# CH32V003F4P6-R0-1v1.net
KiCad netlist of a schematic drawn in Altium Designer
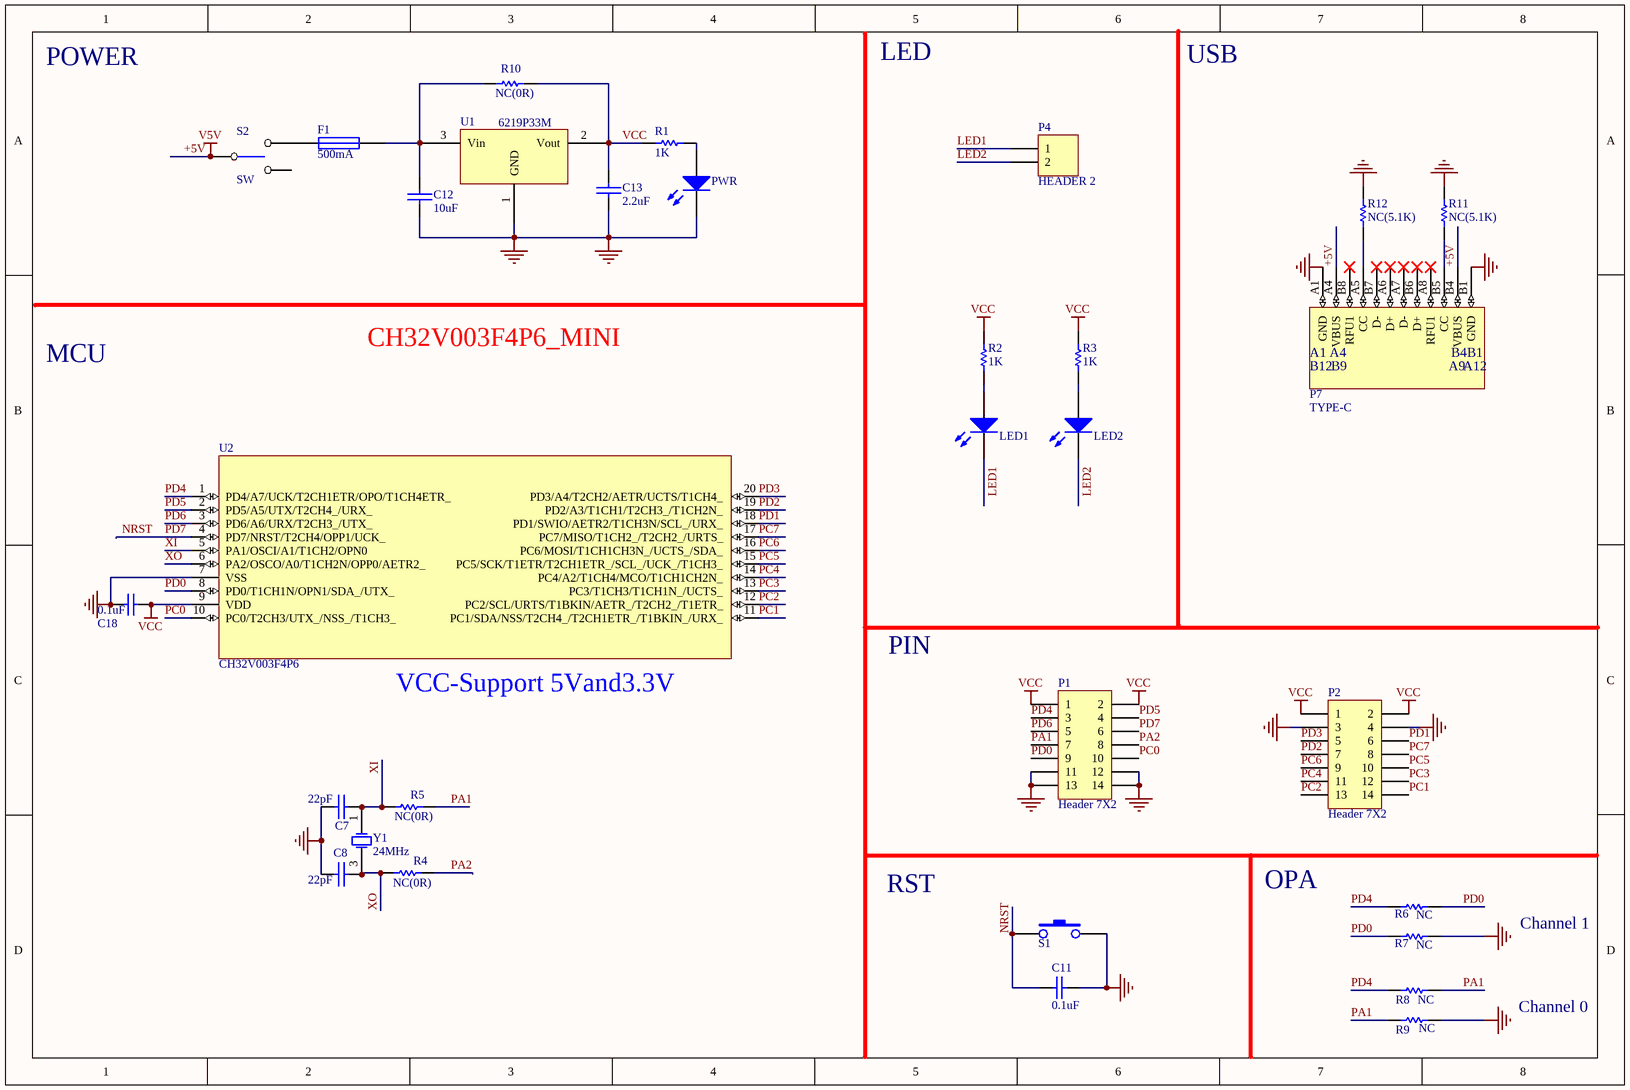
[diagram p0: CH32V003F4P6-R0-1v1.SchDoc]

(export (version "E")
  (design (tool "Eeschema 10.0.6"))
  (components
    (comp (ref "C7")
      (value "22pF")
      (footprint "0603_C")
      (description "Capacitor")
      (libsource (lib "*") (part "CAP"))
    )
    (comp (ref "C8")
      (value "22pF")
      (footprint "0603_C")
      (description "Capacitor")
      (libsource (lib "*") (part "CAP"))
    )
    (comp (ref "C11")
      (value "0.1uF")
      (footprint "0603_C")
      (description "Capacitor")
      (fields (field (name "PUBLISHER") "Altium Limited"))
      (libsource (lib "*") (part "Cap"))
    )
    (comp (ref "C12")
      (value "10uF")
      (footprint "3216_C")
      (description "Capacitor")
      (libsource (lib "wch_sch_others") (part "CAP"))
    )
    (comp (ref "C13")
      (value "2.2uF")
      (footprint "0603_C")
      (description "Capacitor")
      (libsource (lib "wch_sch_others") (part "CAP"))
    )
    (comp (ref "C18")
      (value "0.1uF")
      (footprint "0603_C")
      (description "Capacitor")
      (fields (field (name "PUBLISHER") "Altium Limited"))
      (libsource (lib "*") (part "Cap"))
    )
    (comp (ref "F1")
      (value "500mA")
      (footprint "0603")
      (description "Fuse")
      (libsource (lib "*") (part "FUSE1"))
    )
    (comp (ref "LED1")
      (value "LED1   blue")
      (footprint "0603+")
      (description "Typical INFRARED GaAs LED")
      (fields (field (name "PUBLISHER") "Altium Limited"))
      (libsource (lib "*") (part "LED0"))
    )
    (comp (ref "LED2")
      (value "LED2  blue")
      (footprint "0603+")
      (description "Typical INFRARED GaAs LED")
      (fields (field (name "PUBLISHER") "Altium Limited"))
      (libsource (lib "*") (part "LED0"))
    )
    (comp (ref "P1")
      (value "Header 7X2")
      (footprint "IDC14-2.54mm")
      (description "Header, 7-Pin, Dual row")
      (fields (field (name "PUBLISHER") "Altium Limited"))
      (libsource (lib "Miscellaneous Connectors") (part "Header 7X2"))
    )
    (comp (ref "P2")
      (value "Header 7X2")
      (footprint "IDC14-2.54mm")
      (description "Header, 7-Pin, Dual row")
      (fields (field (name "PUBLISHER") "Altium Limited"))
      (libsource (lib "Miscellaneous Connectors") (part "Header 7X2"))
    )
    (comp (ref "P4")
      (value "HEADER 2")
      (footprint "MYPCB:SIP2-2.54mm")
      (description "Header, 2-Pin")
      (libsource (lib "wch_sch_others") (part "HEADER 2"))
    )
    (comp (ref "P7")
      (value "TYPE-C")
      (footprint "TYPE-C-Receptacle-2.0")
      (libsource (lib "*") (part "TYPE-C1"))
    )
    (comp (ref "PWR")
      (value "POWER  red")
      (footprint "0603+")
      (description "Typical INFRARED GaAs LED")
      (fields (field (name "PUBLISHER") "Altium Limited"))
      (libsource (lib "") (part "LED0_1"))
    )
    (comp (ref "R1")
      (value "1K")
      (footprint "0603")
      (description "Semiconductor Resistor")
      (fields (field (name "PUBLISHER") "Altium Limited"))
      (libsource (lib "*") (part "Res Semi"))
    )
    (comp (ref "R2")
      (value "1K")
      (footprint "0603")
      (description "Semiconductor Resistor")
      (fields (field (name "PUBLISHER") "Altium Limited"))
      (libsource (lib "*") (part "Res Semi"))
    )
    (comp (ref "R3")
      (value "1K")
      (footprint "0603")
      (description "Semiconductor Resistor")
      (fields (field (name "PUBLISHER") "Altium Limited"))
      (libsource (lib "*") (part "Res Semi"))
    )
    (comp (ref "R4")
      (value "NC(0R)")
      (footprint "0603")
      (description "Semiconductor Resistor")
      (fields (field (name "Comment") "0R") (field (name "PUBLISHER") "Altium Limited"))
      (libsource (lib "*") (part "Res Semi"))
    )
    (comp (ref "R5")
      (value "NC(0R)")
      (footprint "0603")
      (description "Semiconductor Resistor")
      (fields (field (name "Comment") "0R") (field (name "PUBLISHER") "Altium Limited"))
      (libsource (lib "*") (part "Res Semi"))
    )
    (comp (ref "R6")
      (value "NC")
      (footprint "0603")
      (description "Semiconductor Resistor")
      (fields (field (name "Comment") "0R") (field (name "PUBLISHER") "Altium Limited"))
      (libsource (lib "*") (part "Res Semi"))
    )
    (comp (ref "R7")
      (value "NC")
      (footprint "0603")
      (description "Semiconductor Resistor")
      (fields (field (name "Comment") "0R") (field (name "PUBLISHER") "Altium Limited"))
      (libsource (lib "*") (part "Res Semi"))
    )
    (comp (ref "R8")
      (value "NC")
      (footprint "0603")
      (description "Semiconductor Resistor")
      (fields (field (name "Comment") "0R") (field (name "PUBLISHER") "Altium Limited"))
      (libsource (lib "*") (part "Res Semi"))
    )
    (comp (ref "R9")
      (value "NC")
      (footprint "0603")
      (description "Semiconductor Resistor")
      (fields (field (name "Comment") "0R") (field (name "PUBLISHER") "Altium Limited"))
      (libsource (lib "*") (part "Res Semi"))
    )
    (comp (ref "R10")
      (value "NC(0R)")
      (footprint "0603")
      (description "Semiconductor Resistor")
      (fields (field (name "Comment") "0R") (field (name "PUBLISHER") "Altium Limited"))
      (libsource (lib "*") (part "Res Semi"))
    )
    (comp (ref "R11")
      (value "NC(5.1K)")
      (footprint "0603")
      (description "Semiconductor Resistor")
      (fields (field (name "Comment") "0R") (field (name "PUBLISHER") "Altium Limited"))
      (libsource (lib "*") (part "Res Semi"))
    )
    (comp (ref "R12")
      (value "NC(5.1K)")
      (footprint "0603")
      (description "Semiconductor Resistor")
      (fields (field (name "Comment") "0R") (field (name "PUBLISHER") "Altium Limited"))
      (libsource (lib "*") (part "Res Semi"))
    )
    (comp (ref "S1") (value "NRST") (footprint "SMD_6.1x3.65x2.5mm-KEY") (libsource (lib "*") (part "KEY")))
    (comp (ref "S2") (value "SW") (footprint "SW1") (libsource (lib "*") (part "SW")))
    (comp (ref "U1")
      (value "6219P33M")
      (footprint "SOT-23")
      (libsource (lib "wch_sch_others") (part "6219P33M"))
    )
    (comp (ref "U2")
      (value "CH32V003F4P6")
      (description "RISC-V MCU, 48MHz")
      (libsource (lib "MEXXX") (part "CH32V003F4P6"))
    )
    (comp (ref "Y1")
      (value "24MHz")
      (footprint "XT3225")
      (description "Crystal Oscillator")
      (fields (field (name "PUBLISHER") "Altium Limited"))
      (libsource (lib "*") (part "XTAL"))
    )
  )
  (nets
    (net (code "1") (name "/LED1") (class "Default")
      (node (ref "LED1") (pin "2") (pinfunction "K_2") (pintype "passive"))
      (node (ref "P4") (pin "1") (pinfunction "1_1") (pintype "passive"))
    )
    (net (code "2") (name "/LED2") (class "Default")
      (node (ref "LED2") (pin "2") (pinfunction "K_2") (pintype "passive"))
      (node (ref "P4") (pin "2") (pinfunction "2_2") (pintype "passive"))
    )
    (net (code "3") (name "/NRST") (class "Default")
      (node (ref "C11") (pin "2") (pinfunction "2_2") (pintype "passive"))
      (node (ref "P1") (pin "6") (pinfunction "6_6") (pintype "passive"))
      (node (ref "S1") (pin "1") (pinfunction "1_1") (pintype "passive"))
      (node (ref "U2") (pin "4") (pinfunction "PD7/NRST/T2CH4/OPP1/UCK__4") (pintype "bidirectional"))
    )
    (net (code "4") (name "/PA1") (class "Default")
      (node (ref "P1") (pin "7") (pinfunction "7_7") (pintype "passive"))
      (node (ref "R5") (pin "2") (pinfunction "2_2") (pintype "passive"))
      (node (ref "R8") (pin "2") (pinfunction "2_2") (pintype "passive"))
      (node (ref "R9") (pin "1") (pinfunction "1_1") (pintype "passive"))
    )
    (net (code "5") (name "/PA2") (class "Default")
      (node (ref "P1") (pin "8") (pinfunction "8_8") (pintype "passive"))
      (node (ref "R4") (pin "2") (pinfunction "2_2") (pintype "passive"))
    )
    (net (code "6") (name "/PC0") (class "Default")
      (node (ref "P1") (pin "10") (pinfunction "10_10") (pintype "passive"))
      (node (ref "U2") (pin "10") (pinfunction "PC0/T2CH3/UTX_/NSS_/T1CH3__10") (pintype "bidirectional"))
    )
    (net (code "7") (name "/PC1") (class "Default")
      (node (ref "P2") (pin "14") (pinfunction "14_14") (pintype "passive"))
      (node (ref "U2") (pin "11") (pinfunction "PC1/SDA/NSS/T2CH4_/T2CH1ETR_/T1BKIN_/URX__11") (pintype "bidirectional"))
    )
    (net (code "8") (name "/PC2") (class "Default")
      (node (ref "P2") (pin "13") (pinfunction "13_13") (pintype "passive"))
      (node (ref "U2") (pin "12") (pinfunction "PC2/SCL/URTS/T1BKIN/AETR_/T2CH2_/T1ETR__12") (pintype "bidirectional"))
    )
    (net (code "9") (name "/PC3") (class "Default")
      (node (ref "P2") (pin "12") (pinfunction "12_12") (pintype "passive"))
      (node (ref "U2") (pin "13") (pinfunction "PC3/T1CH3/T1CH1N_/UCTS__13") (pintype "bidirectional"))
    )
    (net (code "10") (name "/PC4") (class "Default")
      (node (ref "P2") (pin "11") (pinfunction "11_11") (pintype "passive"))
      (node (ref "U2") (pin "14") (pinfunction "PC4/A2/T1CH4/MCO/T1CH1CH2N__14") (pintype "bidirectional"))
    )
    (net (code "11") (name "/PC5") (class "Default")
      (node (ref "P2") (pin "10") (pinfunction "10_10") (pintype "passive"))
      (node (ref "U2") (pin "15") (pinfunction "PC5/SCK/T1ETR/T2CH1ETR_/SCL_/UCK_/T1CH3__15") (pintype "bidirectional"))
    )
    (net (code "12") (name "/PC6") (class "Default")
      (node (ref "P2") (pin "9") (pinfunction "9_9") (pintype "passive"))
      (node (ref "U2") (pin "16") (pinfunction "PC6/MOSI/T1CH1CH3N_/UCTS_/SDA__16") (pintype "bidirectional"))
    )
    (net (code "13") (name "/PC7") (class "Default")
      (node (ref "P2") (pin "8") (pinfunction "8_8") (pintype "passive"))
      (node (ref "U2") (pin "17") (pinfunction "PC7/MISO/T1CH2_/T2CH2_/URTS__17") (pintype "bidirectional"))
    )
    (net (code "14") (name "/PD0") (class "Default")
      (node (ref "P1") (pin "9") (pinfunction "9_9") (pintype "passive"))
      (node (ref "R6") (pin "2") (pinfunction "2_2") (pintype "passive"))
      (node (ref "R7") (pin "1") (pinfunction "1_1") (pintype "passive"))
      (node (ref "U2") (pin "8") (pinfunction "PD0/T1CH1N/OPN1/SDA_/UTX__8") (pintype "bidirectional"))
    )
    (net (code "15") (name "/PD1") (class "Default")
      (node (ref "P2") (pin "6") (pinfunction "6_6") (pintype "passive"))
      (node (ref "U2") (pin "18") (pinfunction "PD1/SWIO/AETR2/T1CH3N/SCL_/URX__18") (pintype "bidirectional"))
    )
    (net (code "16") (name "/PD2") (class "Default")
      (node (ref "P2") (pin "7") (pinfunction "7_7") (pintype "passive"))
      (node (ref "U2") (pin "19") (pinfunction "PD2/A3/T1CH1/T2CH3_/T1CH2N__19") (pintype "bidirectional"))
    )
    (net (code "17") (name "/PD3") (class "Default")
      (node (ref "P2") (pin "5") (pinfunction "5_5") (pintype "passive"))
      (node (ref "U2") (pin "20") (pinfunction "PD3/A4/T2CH2/AETR/UCTS/T1CH4__20") (pintype "bidirectional"))
    )
    (net (code "18") (name "/PD4") (class "Default")
      (node (ref "P1") (pin "3") (pinfunction "3_3") (pintype "passive"))
      (node (ref "R6") (pin "1") (pinfunction "1_1") (pintype "passive"))
      (node (ref "R8") (pin "1") (pinfunction "1_1") (pintype "passive"))
      (node (ref "U2") (pin "1") (pinfunction "PD4/A7/UCK/T2CH1ETR/OPO/T1CH4ETR__1") (pintype "bidirectional"))
    )
    (net (code "19") (name "/PD5") (class "Default")
      (node (ref "P1") (pin "4") (pinfunction "4_4") (pintype "passive"))
      (node (ref "U2") (pin "2") (pinfunction "PD5/A5/UTX/T2CH4_/URX__2") (pintype "bidirectional"))
    )
    (net (code "20") (name "/PD6") (class "Default")
      (node (ref "P1") (pin "5") (pinfunction "5_5") (pintype "passive"))
      (node (ref "U2") (pin "3") (pinfunction "PD6/A6/URX/T2CH3_/UTX__3") (pintype "bidirectional"))
    )
    (net (code "21") (name "/XI") (class "Default")
      (node (ref "C7") (pin "2") (pinfunction "2_2") (pintype "passive"))
      (node (ref "R5") (pin "1") (pinfunction "1_1") (pintype "passive"))
      (node (ref "U2") (pin "5") (pinfunction "PA1/OSCI/A1/T1CH2/OPN0_5") (pintype "bidirectional"))
      (node (ref "Y1") (pin "1") (pinfunction "OSC1_1") (pintype "passive"))
    )
    (net (code "22") (name "/XO") (class "Default")
      (node (ref "C8") (pin "2") (pinfunction "2_2") (pintype "passive"))
      (node (ref "R4") (pin "1") (pinfunction "1_1") (pintype "passive"))
      (node (ref "U2") (pin "6") (pinfunction "PA2/OSCO/A0/T1CH2N/OPP0/AETR2__6") (pintype "bidirectional"))
      (node (ref "Y1") (pin "3") (pinfunction "OSC2_3") (pintype "passive"))
    )
    (net (code "23") (name "GND") (class "Default")
      (node (ref "C11") (pin "1") (pinfunction "1_1") (pintype "passive"))
      (node (ref "C12") (pin "2") (pinfunction "2_2") (pintype "passive"))
      (node (ref "C13") (pin "1") (pinfunction "1_1") (pintype "passive"))
      (node (ref "C18") (pin "1") (pinfunction "1_1") (pintype "passive"))
      (node (ref "C7") (pin "1") (pinfunction "1_1") (pintype "passive"))
      (node (ref "C8") (pin "1") (pinfunction "1_1") (pintype "passive"))
      (node (ref "P1") (pin "11") (pinfunction "11_11") (pintype "passive"))
      (node (ref "P1") (pin "12") (pinfunction "12_12") (pintype "passive"))
      (node (ref "P1") (pin "13") (pinfunction "13_13") (pintype "passive"))
      (node (ref "P1") (pin "14") (pinfunction "14_14") (pintype "passive"))
      (node (ref "P2") (pin "3") (pinfunction "3_3") (pintype "passive"))
      (node (ref "P2") (pin "4") (pinfunction "4_4") (pintype "passive"))
      (node (ref "P7") (pin "A1") (pinfunction "GND_A1") (pintype "bidirectional"))
      (node (ref "P7") (pin "B1") (pinfunction "GND_B1") (pintype "bidirectional"))
      (node (ref "PWR") (pin "2") (pinfunction "K_2") (pintype "passive"))
      (node (ref "R11") (pin "2") (pinfunction "2_2") (pintype "passive"))
      (node (ref "R12") (pin "2") (pinfunction "2_2") (pintype "passive"))
      (node (ref "R7") (pin "2") (pinfunction "2_2") (pintype "passive"))
      (node (ref "R9") (pin "2") (pinfunction "2_2") (pintype "passive"))
      (node (ref "S1") (pin "2") (pinfunction "2_2") (pintype "passive"))
      (node (ref "U1") (pin "1") (pinfunction "GND_1") (pintype "passive"))
      (node (ref "U2") (pin "7") (pinfunction "VSS_7") (pintype "power_in"))
    )
    (net (code "24") (name "Net-(F1-Pad1)") (class "Default")
      (node (ref "F1") (pin "1") (pinfunction "1_1") (pintype "passive"))
      (node (ref "S2") (pin "3") (pinfunction "3_3") (pintype "passive"))
    )
    (net (code "25") (name "Net-(LED1-A)") (class "Default")
      (node (ref "LED1") (pin "1") (pinfunction "A_1") (pintype "passive"))
      (node (ref "R2") (pin "2") (pinfunction "2_2") (pintype "passive"))
    )
    (net (code "26") (name "Net-(LED2-A)") (class "Default")
      (node (ref "LED2") (pin "1") (pinfunction "A_1") (pintype "passive"))
      (node (ref "R3") (pin "2") (pinfunction "2_2") (pintype "passive"))
    )
    (net (code "27") (name "Net-(P7-CC-PadA5)") (class "Default")
      (node (ref "P7") (pin "A5") (pinfunction "CC_A5") (pintype "bidirectional"))
      (node (ref "R12") (pin "1") (pinfunction "1_1") (pintype "passive"))
    )
    (net (code "28") (name "Net-(P7-CC-PadB5)") (class "Default")
      (node (ref "P7") (pin "B5") (pinfunction "CC_B5") (pintype "bidirectional"))
      (node (ref "R11") (pin "1") (pinfunction "1_1") (pintype "passive"))
    )
    (net (code "29") (name "Net-(PWR-A)") (class "Default")
      (node (ref "PWR") (pin "1") (pinfunction "A_1") (pintype "passive"))
      (node (ref "R1") (pin "1") (pinfunction "1_1") (pintype "passive"))
    )
    (net (code "30") (name "Net-(U1-Vin)") (class "Default")
      (node (ref "C12") (pin "1") (pinfunction "1_1") (pintype "passive"))
      (node (ref "F1") (pin "2") (pinfunction "2_2") (pintype "passive"))
      (node (ref "R10") (pin "1") (pinfunction "1_1") (pintype "passive"))
      (node (ref "U1") (pin "3") (pinfunction "Vin_3") (pintype "passive"))
    )
    (net (code "31") (name "V5V") (class "Default")
      (node (ref "P7") (pin "A4") (pinfunction "VBUS_A4") (pintype "bidirectional"))
      (node (ref "P7") (pin "B4") (pinfunction "VBUS_B4") (pintype "bidirectional"))
      (node (ref "S2") (pin "1") (pinfunction "1_1") (pintype "passive"))
    )
    (net (code "32") (name "VCC") (class "Default")
      (node (ref "C13") (pin "2") (pinfunction "2_2") (pintype "passive"))
      (node (ref "C18") (pin "2") (pinfunction "2_2") (pintype "passive"))
      (node (ref "P1") (pin "1") (pinfunction "1_1") (pintype "passive"))
      (node (ref "P1") (pin "2") (pinfunction "2_2") (pintype "passive"))
      (node (ref "P2") (pin "1") (pinfunction "1_1") (pintype "passive"))
      (node (ref "P2") (pin "2") (pinfunction "2_2") (pintype "passive"))
      (node (ref "R1") (pin "2") (pinfunction "2_2") (pintype "passive"))
      (node (ref "R10") (pin "2") (pinfunction "2_2") (pintype "passive"))
      (node (ref "R2") (pin "1") (pinfunction "1_1") (pintype "passive"))
      (node (ref "R3") (pin "1") (pinfunction "1_1") (pintype "passive"))
      (node (ref "U1") (pin "2") (pinfunction "Vout_2") (pintype "passive"))
      (node (ref "U2") (pin "9") (pinfunction "VDD_9") (pintype "power_in"))
    )
    (net (code "33") (name "unconnected-(P7-D+-PadA6)") (class "Default")
      (node (ref "P7") (pin "A6") (pinfunction "D+_A6") (pintype "bidirectional+no_connect"))
    )
    (net (code "34") (name "unconnected-(P7-D+-PadB6)") (class "Default")
      (node (ref "P7") (pin "B6") (pinfunction "D+_B6") (pintype "bidirectional+no_connect"))
    )
    (net (code "35") (name "unconnected-(P7-D--PadA7)") (class "Default")
      (node (ref "P7") (pin "A7") (pinfunction "D-_A7") (pintype "bidirectional+no_connect"))
    )
    (net (code "36") (name "unconnected-(P7-D--PadB7)") (class "Default")
      (node (ref "P7") (pin "B7") (pinfunction "D-_B7") (pintype "bidirectional+no_connect"))
    )
    (net (code "37") (name "unconnected-(P7-RFU1-PadA8)") (class "Default")
      (node (ref "P7") (pin "A8") (pinfunction "RFU1_A8") (pintype "bidirectional+no_connect"))
    )
    (net (code "38") (name "unconnected-(P7-RFU1-PadB8)") (class "Default")
      (node (ref "P7") (pin "B8") (pinfunction "RFU1_B8") (pintype "bidirectional+no_connect"))
    )
    (net (code "39") (name "unconnected-(S2-Pad2)") (class "Default")
      (node (ref "S2") (pin "2") (pinfunction "2_2") (pintype "passive"))
    )
  )
)
